# 1-Schematic_Final_Assigment.net
KiCad netlist of a schematic drawn in EasyEDA
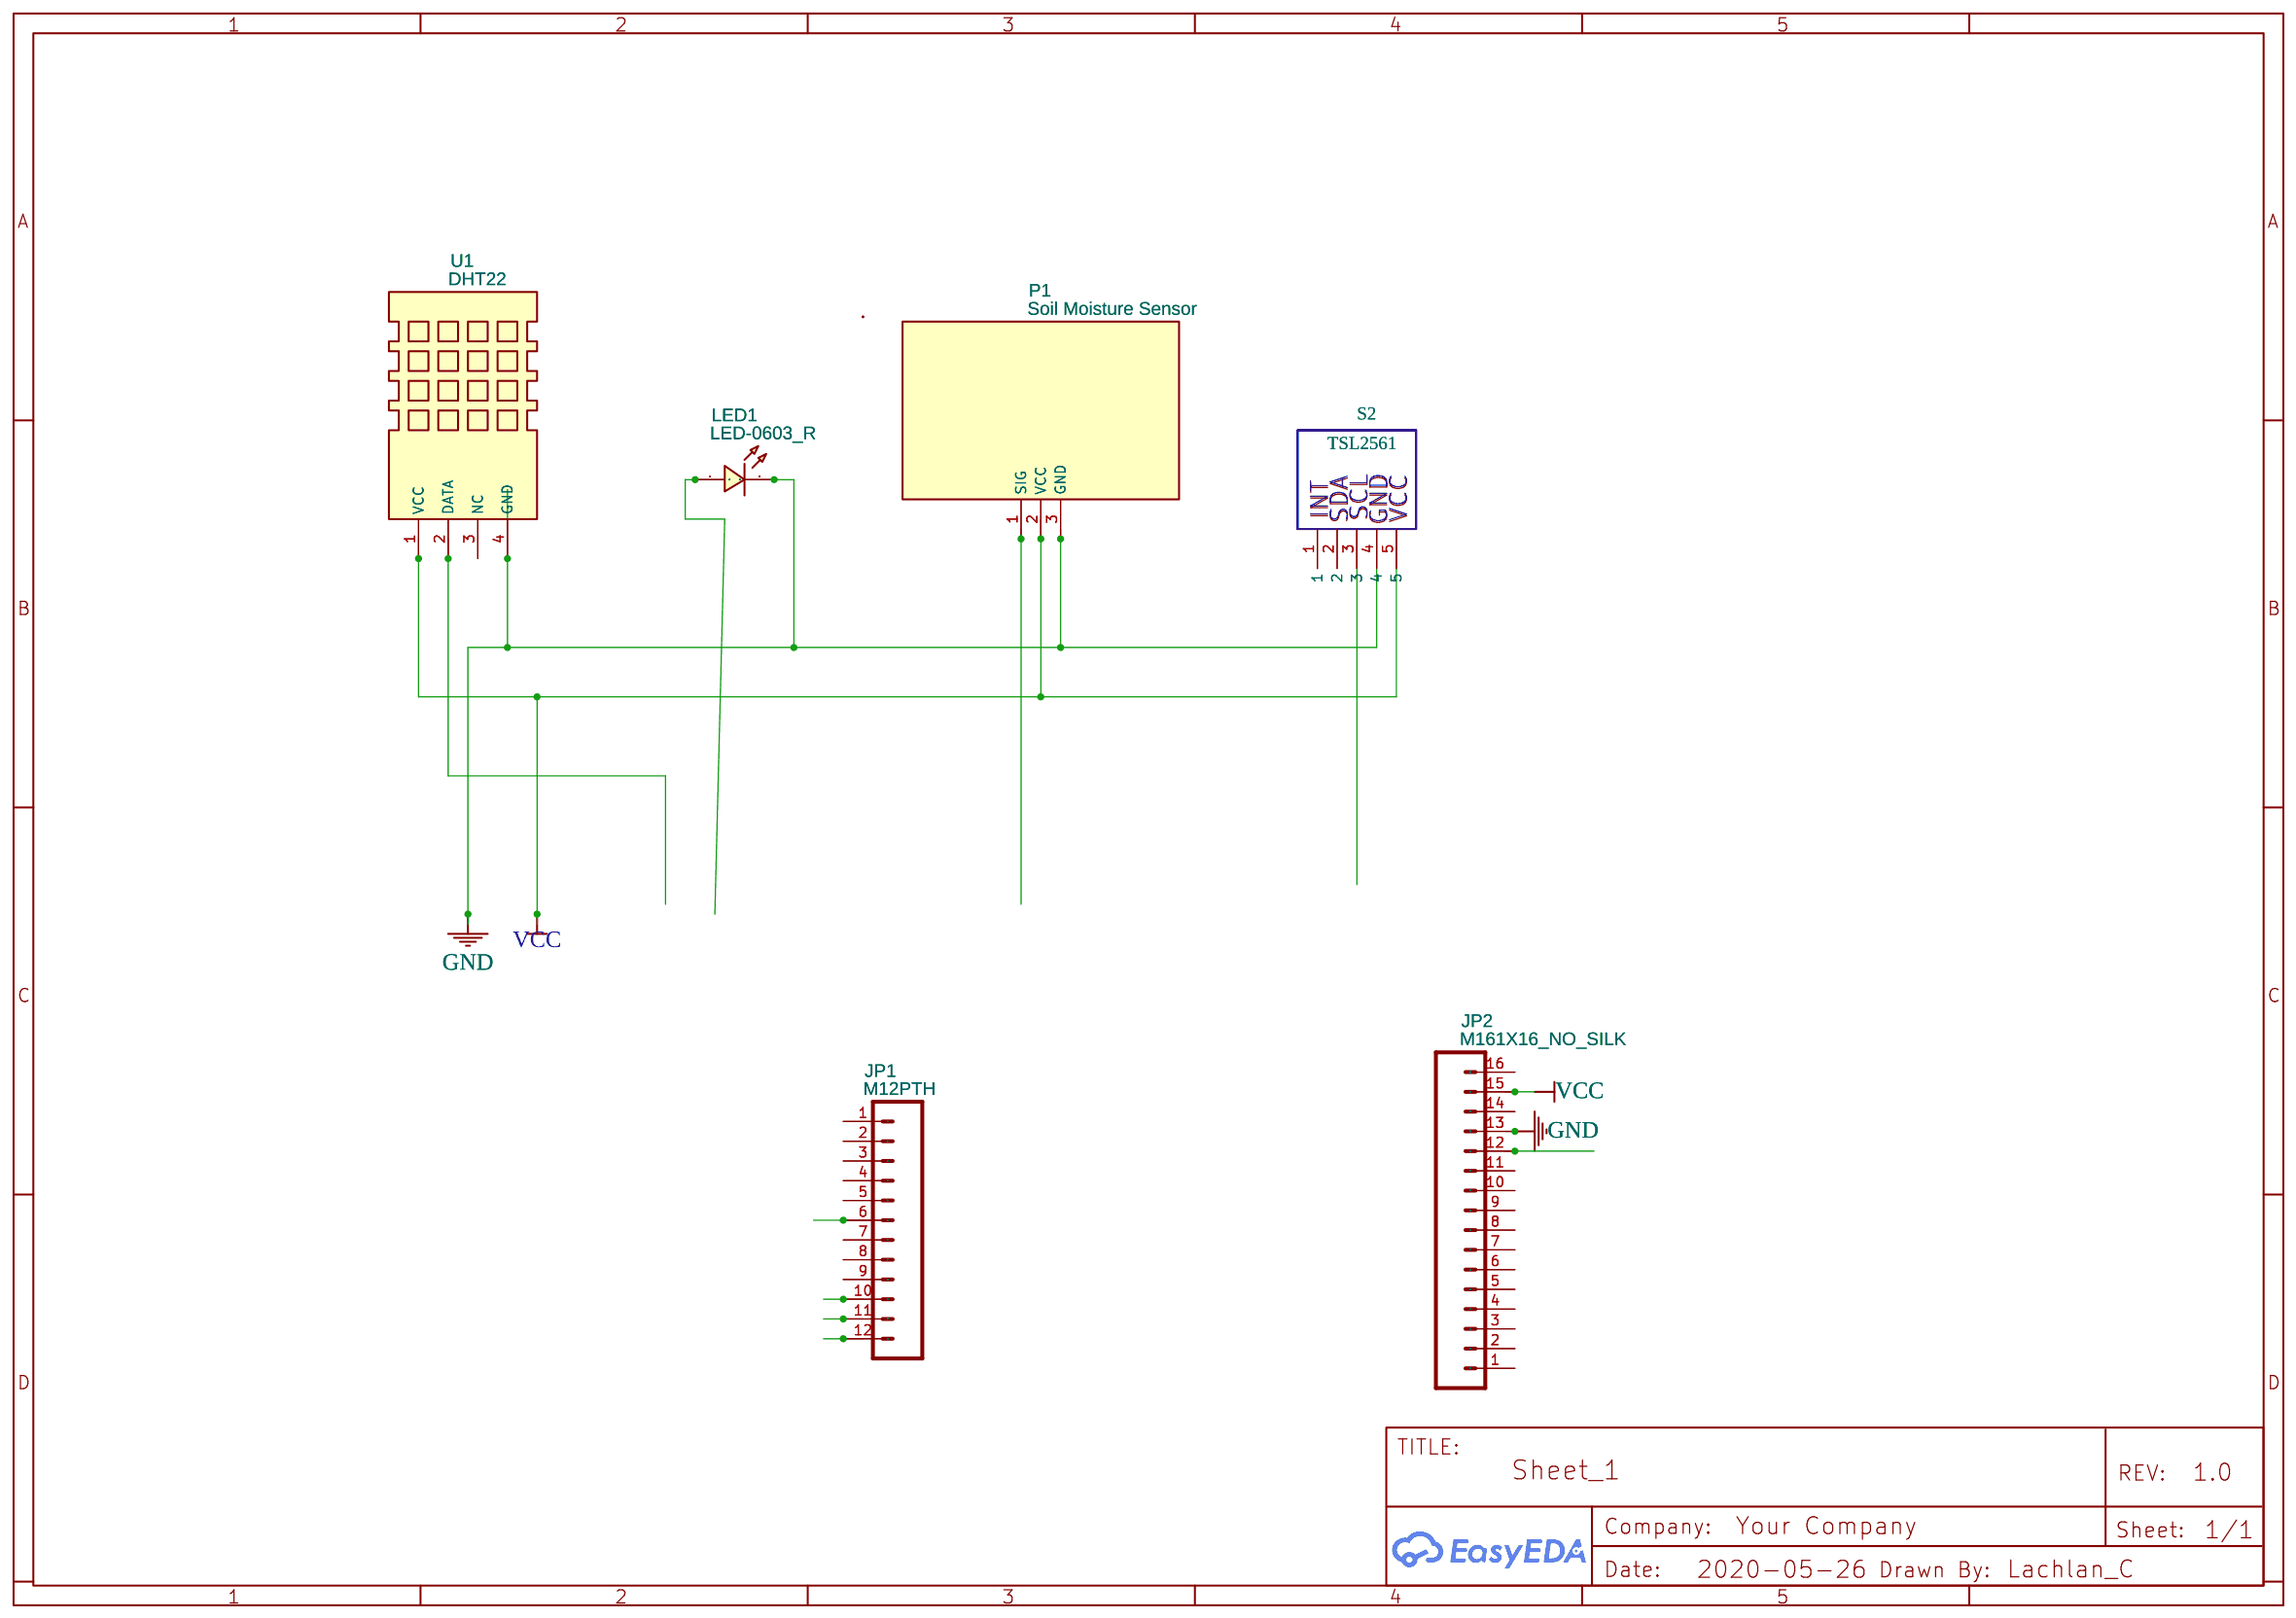
[diagram p0: schematic sheet]

(export (version "E")
  (design (tool "Eeschema 10.0.6"))
  (components
    (comp (ref "JP1") (value "M12PTH") (libsource (lib "") (part "M12PTH")))
    (comp (ref "JP2") (value "M161X16_NO_SILK") (libsource (lib "") (part "M161X16_NO_SILK")))
    (comp (ref "LED1")
      (value "LED-0603_R")
      (fields
        (field (name "BOM_Manufacturer Part") "19-217/R6C-AL1M2VY/3T")
        (field (name "BOM_Supplier Part") "C72044")
      )
      (libsource (lib "") (part "LED-0603_R"))
    )
    (comp (ref "P1")
      (value "Soil Moisture Sensor")
      (fields (field (name "BOM_Supplier Part") "12587"))
      (libsource (lib "") (part "Soil Moisture Sensor"))
    )
    (comp (ref "S2") (value "TSL2561") (libsource (lib "") (part "Unknown_680_-555")))
    (comp (ref "U1")
      (value "DHT22")
      (fields (field (name "BOM_Supplier Part") "PRODUCT ID: 385"))
      (libsource (lib "") (part "DHT22"))
    )
  )
  (nets
    (net (code "1") (name "GND") (class "Default")
      (node (ref "JP2") (pin "13") (pinfunction "13_13") (pintype "unspecified"))
      (node (ref "LED1") (pin "2") (pinfunction "2_2") (pintype "unspecified"))
      (node (ref "P1") (pin "3") (pinfunction "GND_3") (pintype "unspecified"))
      (node (ref "S2") (pin "4") (pinfunction "4_4") (pintype "unspecified"))
      (node (ref "U1") (pin "4") (pinfunction "GND_4") (pintype "unspecified"))
    )
    (net (code "2") (name "VCC") (class "Default")
      (node (ref "JP2") (pin "15") (pinfunction "15_15") (pintype "unspecified"))
      (node (ref "P1") (pin "2") (pinfunction "VCC_2") (pintype "unspecified"))
      (node (ref "S2") (pin "5") (pinfunction "5_5") (pintype "unspecified"))
      (node (ref "U1") (pin "1") (pinfunction "VCC_1") (pintype "unspecified"))
    )
    (net (code "3") (name "unconnected-(JP1-Pad1)") (class "Default")
      (node (ref "JP1") (pin "1") (pinfunction "1_1") (pintype "unspecified"))
    )
    (net (code "4") (name "unconnected-(JP1-Pad2)") (class "Default")
      (node (ref "JP1") (pin "2") (pinfunction "2_2") (pintype "unspecified"))
    )
    (net (code "5") (name "unconnected-(JP1-Pad3)") (class "Default")
      (node (ref "JP1") (pin "3") (pinfunction "3_3") (pintype "unspecified"))
    )
    (net (code "6") (name "unconnected-(JP1-Pad4)") (class "Default")
      (node (ref "JP1") (pin "4") (pinfunction "4_4") (pintype "unspecified"))
    )
    (net (code "7") (name "unconnected-(JP1-Pad5)") (class "Default")
      (node (ref "JP1") (pin "5") (pinfunction "5_5") (pintype "unspecified"))
    )
    (net (code "8") (name "unconnected-(JP1-Pad6)") (class "Default")
      (node (ref "JP1") (pin "6") (pinfunction "6_6") (pintype "unspecified"))
    )
    (net (code "9") (name "unconnected-(JP1-Pad7)") (class "Default")
      (node (ref "JP1") (pin "7") (pinfunction "7_7") (pintype "unspecified"))
    )
    (net (code "10") (name "unconnected-(JP1-Pad8)") (class "Default")
      (node (ref "JP1") (pin "8") (pinfunction "8_8") (pintype "unspecified"))
    )
    (net (code "11") (name "unconnected-(JP1-Pad9)") (class "Default")
      (node (ref "JP1") (pin "9") (pinfunction "9_9") (pintype "unspecified"))
    )
    (net (code "12") (name "unconnected-(JP1-Pad10)") (class "Default")
      (node (ref "JP1") (pin "10") (pinfunction "10_10") (pintype "unspecified"))
    )
    (net (code "13") (name "unconnected-(JP1-Pad11)") (class "Default")
      (node (ref "JP1") (pin "11") (pinfunction "11_11") (pintype "unspecified"))
    )
    (net (code "14") (name "unconnected-(JP1-Pad12)") (class "Default")
      (node (ref "JP1") (pin "12") (pinfunction "12_12") (pintype "unspecified"))
    )
    (net (code "15") (name "unconnected-(JP2-Pad1)") (class "Default")
      (node (ref "JP2") (pin "1") (pinfunction "1_1") (pintype "unspecified"))
    )
    (net (code "16") (name "unconnected-(JP2-Pad2)") (class "Default")
      (node (ref "JP2") (pin "2") (pinfunction "2_2") (pintype "unspecified"))
    )
    (net (code "17") (name "unconnected-(JP2-Pad3)") (class "Default")
      (node (ref "JP2") (pin "3") (pinfunction "3_3") (pintype "unspecified"))
    )
    (net (code "18") (name "unconnected-(JP2-Pad4)") (class "Default")
      (node (ref "JP2") (pin "4") (pinfunction "4_4") (pintype "unspecified"))
    )
    (net (code "19") (name "unconnected-(JP2-Pad5)") (class "Default")
      (node (ref "JP2") (pin "5") (pinfunction "5_5") (pintype "unspecified"))
    )
    (net (code "20") (name "unconnected-(JP2-Pad6)") (class "Default")
      (node (ref "JP2") (pin "6") (pinfunction "6_6") (pintype "unspecified"))
    )
    (net (code "21") (name "unconnected-(JP2-Pad7)") (class "Default")
      (node (ref "JP2") (pin "7") (pinfunction "7_7") (pintype "unspecified"))
    )
    (net (code "22") (name "unconnected-(JP2-Pad8)") (class "Default")
      (node (ref "JP2") (pin "8") (pinfunction "8_8") (pintype "unspecified"))
    )
    (net (code "23") (name "unconnected-(JP2-Pad9)") (class "Default")
      (node (ref "JP2") (pin "9") (pinfunction "9_9") (pintype "unspecified"))
    )
    (net (code "24") (name "unconnected-(JP2-Pad10)") (class "Default")
      (node (ref "JP2") (pin "10") (pinfunction "10_10") (pintype "unspecified"))
    )
    (net (code "25") (name "unconnected-(JP2-Pad11)") (class "Default")
      (node (ref "JP2") (pin "11") (pinfunction "11_11") (pintype "unspecified"))
    )
    (net (code "26") (name "unconnected-(JP2-Pad12)") (class "Default")
      (node (ref "JP2") (pin "12") (pinfunction "12_12") (pintype "unspecified"))
    )
    (net (code "27") (name "unconnected-(JP2-Pad14)") (class "Default")
      (node (ref "JP2") (pin "14") (pinfunction "14_14") (pintype "unspecified"))
    )
    (net (code "28") (name "unconnected-(JP2-Pad16)") (class "Default")
      (node (ref "JP2") (pin "16") (pinfunction "16_16") (pintype "unspecified"))
    )
    (net (code "29") (name "unconnected-(LED1-Pad1)") (class "Default")
      (node (ref "LED1") (pin "1") (pinfunction "1_1") (pintype "unspecified"))
    )
    (net (code "30") (name "unconnected-(P1-SIG-Pad1)") (class "Default")
      (node (ref "P1") (pin "1") (pinfunction "SIG_1") (pintype "unspecified"))
    )
    (net (code "31") (name "unconnected-(S2-Pad1)") (class "Default")
      (node (ref "S2") (pin "1") (pinfunction "1_1") (pintype "unspecified"))
    )
    (net (code "32") (name "unconnected-(S2-Pad2)") (class "Default")
      (node (ref "S2") (pin "2") (pinfunction "2_2") (pintype "unspecified"))
    )
    (net (code "33") (name "unconnected-(S2-Pad3)") (class "Default")
      (node (ref "S2") (pin "3") (pinfunction "3_3") (pintype "unspecified"))
    )
    (net (code "34") (name "unconnected-(U1-DATA-Pad2)") (class "Default")
      (node (ref "U1") (pin "2") (pinfunction "DATA_2") (pintype "unspecified"))
    )
    (net (code "35") (name "unconnected-(U1-NC-Pad3)") (class "Default")
      (node (ref "U1") (pin "3") (pinfunction "NC_3") (pintype "unspecified"))
    )
  )
)
